# INTERRUPTOR.net
KiCad netlist of a schematic drawn in EAGLE
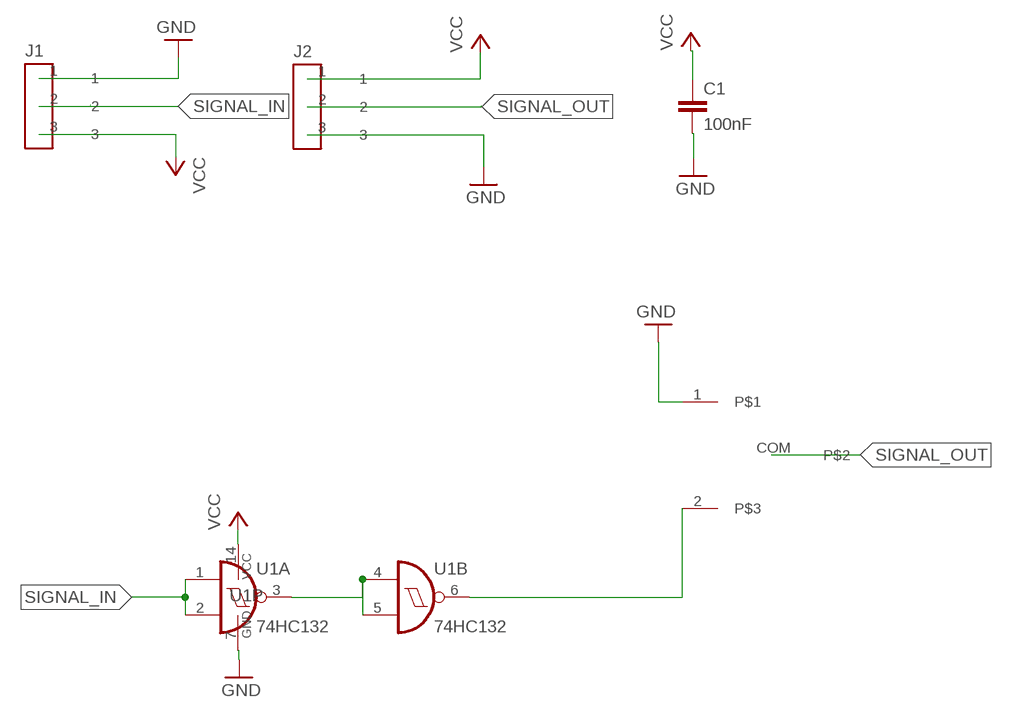
[diagram p0: schematic, sheet 1]

(export (version "E")
  (design (tool "Eeschema 10.0.6"))
  (components
    (comp (ref "C1")
      (value "100nF")
      (footprint "eagle-import:C0805")
      (libsource (lib "eagle-import") (part "C-EUC0805"))
    )
    (comp (ref "J1")
      (value "CONECTOR_MACHO")
      (footprint "eagle-import:MALE")
      (libsource (lib "eagle-import") (part "CONECTOR_MACHO"))
    )
    (comp (ref "J2")
      (value "CONECTOR_FEMEA")
      (footprint "eagle-import:FEMALE")
      (libsource (lib "eagle-import") (part "CONECTOR_FEMEA"))
    )
    (comp (ref "J3")
      (value "SS12F46")
      (footprint "eagle-import:SS12F46")
      (libsource (lib "eagle-import") (part "SS12F46"))
    )
    (comp (ref "U1")
      (value "74HC132")
      (footprint "eagle-import:SO14")
      (libsource (lib "eagle-import") (part "74132DHC"))
    )
  )
  (nets
    (net (code "1") (name "GND") (class "Default")
      (node (ref "C1") (pin "2") (pinfunction "2_2") (pintype "passive"))
      (node (ref "J1") (pin "1") (pinfunction "1_1") (pintype "bidirectional"))
      (node (ref "J2") (pin "3") (pinfunction "3_3") (pintype "bidirectional"))
      (node (ref "J3") (pin "1") (pinfunction "P$1_1") (pintype "bidirectional"))
      (node (ref "U1") (pin "7") (pinfunction "GND_7") (pintype "power_in"))
    )
    (net (code "2") (name "Net-(J3-P$3)") (class "Default")
      (node (ref "J3") (pin "2") (pinfunction "P$3_2") (pintype "bidirectional"))
      (node (ref "U1") (pin "6") (pinfunction "O_6") (pintype "output"))
    )
    (net (code "3") (name "Net-(U1A-O)") (class "Default")
      (node (ref "U1") (pin "3") (pinfunction "O_3") (pintype "output"))
      (node (ref "U1") (pin "4") (pinfunction "I0_4") (pintype "input"))
      (node (ref "U1") (pin "5") (pinfunction "I1_5") (pintype "input"))
    )
    (net (code "4") (name "SIGNAL_IN") (class "Default")
      (node (ref "J1") (pin "2") (pinfunction "2_2") (pintype "bidirectional"))
      (node (ref "U1") (pin "1") (pinfunction "I0_1") (pintype "input"))
      (node (ref "U1") (pin "2") (pinfunction "I1_2") (pintype "input"))
    )
    (net (code "5") (name "SIGNAL_OUT") (class "Default")
      (node (ref "J2") (pin "2") (pinfunction "2_2") (pintype "bidirectional"))
      (node (ref "J3") (pin "COM") (pinfunction "P$2_COM") (pintype "bidirectional"))
    )
    (net (code "6") (name "VCC") (class "Default")
      (node (ref "C1") (pin "1") (pinfunction "1_1") (pintype "passive"))
      (node (ref "J1") (pin "3") (pinfunction "3_3") (pintype "bidirectional"))
      (node (ref "J2") (pin "1") (pinfunction "1_1") (pintype "bidirectional"))
      (node (ref "U1") (pin "14") (pinfunction "VCC_14") (pintype "power_in"))
    )
  )
)
